# Sheet1.net
KiCad netlist of a schematic drawn in Altium Designer
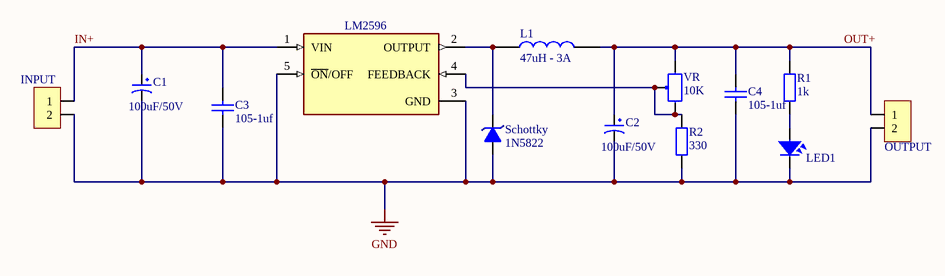
[diagram p0: Sheet1.SchDoc]

(export (version "E")
  (design (tool "Eeschema 10.0.6"))
  (components
    (comp (ref "C1")
      (value "100uF/50V")
      (footprint "CP1.5/3.4")
      (description "Cap 100uF/35V - 470uF/16V")
      (libsource (lib "syhaunguyen") (part "CP3"))
    )
    (comp (ref "C2")
      (value "100uF/50V")
      (footprint "CP1.5/3.4")
      (description "Cap 100uF/35V - 470uF/16V")
      (libsource (lib "syhaunguyen") (part "CP3"))
    )
    (comp (ref "C3")
      (value "105-1uf")
      (footprint "tu gom")
      (description "Cắm")
      (libsource (lib "Altium_Lib_by_KhueNguyenCreator") (part "Tu gom 104 50V"))
    )
    (comp (ref "C4")
      (value "105-1uf")
      (footprint "tu gom")
      (description "Cắm")
      (libsource (lib "Altium_Lib_by_KhueNguyenCreator") (part "Tu gom 104 50V"))
    )
    (comp (ref "INPUT")
      (value "INPUT")
      (footprint "JP 1x2 DT")
      (description "Cắm")
      (libsource (lib "") (part "JP 1x2 2.54 Duc Thang_1"))
    )
    (comp (ref "L1")
      (value "47uH - 3A")
      (footprint "CUON CAM 100uH3A")
      (description "Cắm")
      (libsource (lib "Altium_Lib_by_KhueNguyenCreator") (part "CUON CAM 470uH DIP"))
    )
    (comp (ref "LED1")
      (value "LED")
      (footprint "LED-3")
      (description "LED Single colour Green and Red")
      (libsource (lib "syhaunguyen") (part "LED"))
    )
    (comp (ref "LM2596")
      (value "LM2596-5.0WT")
      (footprint "TO170P1016X444X1572-5")
      (description "Buck Switching Regulator IC Positive Fixed 5V 1 Output 3A TO-220-5")
      (fields (field (name "MF") "Microchip") (field (name "MP") "LM2576-5.0WT"))
      (libsource (lib "LM2576-5.0WT") (part "LM2576-5.0WT"))
    )
    (comp (ref "OUTPUT")
      (value "~")
      (footprint "JP 1x2 DT")
      (description "Cắm")
      (libsource (lib "Altium_Lib_by_KhueNguyenCreator") (part "JP 1x2 2.54 Duc Thang"))
    )
    (comp (ref "R1")
      (value "1k")
      (footprint "R1/4W")
      (description "Resistor 1/4W")
      (libsource (lib "syhaunguyen") (part "R1/4W"))
    )
    (comp (ref "R2")
      (value "330")
      (footprint "R1/4W")
      (description "Resistor 1/4W")
      (libsource (lib "syhaunguyen") (part "R1/4W"))
    )
    (comp (ref "Schottky") (value "1N5822") (footprint "D1A") (libsource (lib "syhaunguyen") (part "Zener")))
    (comp (ref "VR")
      (value "10K")
      (footprint "Bien Tro Vi Chinh Dung")
      (description "Cắm")
      (libsource (lib "Altium_Lib_by_KhueNguyenCreator") (part "Bien Tro Tinh Chinh 10K Dung"))
    )
  )
  (nets
    (net (code "1") (name "/IN+") (class "Default")
      (node (ref "C1") (pin "1") (pinfunction "1_1") (pintype "passive"))
      (node (ref "C3") (pin "1") (pinfunction "1_1") (pintype "passive"))
      (node (ref "INPUT") (pin "1") (pinfunction "1_1") (pintype "passive"))
      (node (ref "LM2596") (pin "1") (pinfunction "VIN_1") (pintype "input"))
    )
    (net (code "2") (name "/OUT+") (class "Default")
      (node (ref "C2") (pin "1") (pinfunction "1_1") (pintype "passive"))
      (node (ref "C4") (pin "1") (pinfunction "1_1") (pintype "passive"))
      (node (ref "L1") (pin "2") (pinfunction "2_2") (pintype "passive"))
      (node (ref "OUTPUT") (pin "1") (pinfunction "1_1") (pintype "passive"))
      (node (ref "R1") (pin "2") (pinfunction "2_2") (pintype "passive"))
      (node (ref "VR") (pin "3") (pinfunction "3_3") (pintype "passive"))
    )
    (net (code "3") (name "GND") (class "Default")
      (node (ref "C1") (pin "2") (pinfunction "2_2") (pintype "passive"))
      (node (ref "C2") (pin "2") (pinfunction "2_2") (pintype "passive"))
      (node (ref "C3") (pin "2") (pinfunction "2_2") (pintype "passive"))
      (node (ref "C4") (pin "2") (pinfunction "2_2") (pintype "passive"))
      (node (ref "INPUT") (pin "2") (pinfunction "2_2") (pintype "passive"))
      (node (ref "LED1") (pin "2") (pinfunction "2_2") (pintype "passive"))
      (node (ref "LM2596") (pin "3") (pinfunction "GND_3") (pintype "power_in"))
      (node (ref "LM2596") (pin "5") (pinfunction "~{ON}/OFF_5") (pintype "input"))
      (node (ref "OUTPUT") (pin "2") (pinfunction "2_2") (pintype "passive"))
      (node (ref "R2") (pin "1") (pinfunction "1_1") (pintype "passive"))
      (node (ref "Schottky") (pin "1") (pinfunction "A_1") (pintype "passive"))
    )
    (net (code "4") (name "Net-(LED1-Pad1)") (class "Default")
      (node (ref "LED1") (pin "1") (pinfunction "1_1") (pintype "passive"))
      (node (ref "R1") (pin "1") (pinfunction "1_1") (pintype "passive"))
    )
    (net (code "5") (name "Net-(LM2596-FEEDBACK)") (class "Default")
      (node (ref "LM2596") (pin "4") (pinfunction "FEEDBACK_4") (pintype "input"))
      (node (ref "R2") (pin "2") (pinfunction "2_2") (pintype "passive"))
      (node (ref "VR") (pin "1") (pinfunction "1_1") (pintype "passive"))
      (node (ref "VR") (pin "2") (pinfunction "2_2") (pintype "passive"))
    )
    (net (code "6") (name "Net-(LM2596-OUTPUT)") (class "Default")
      (node (ref "L1") (pin "1") (pinfunction "1_1") (pintype "passive"))
      (node (ref "LM2596") (pin "2") (pinfunction "OUTPUT_2") (pintype "output"))
      (node (ref "Schottky") (pin "2") (pinfunction "K_2") (pintype "passive"))
    )
  )
)
